# UCirKitUserStudy2.net
KiCad netlist of a schematic drawn in EAGLE
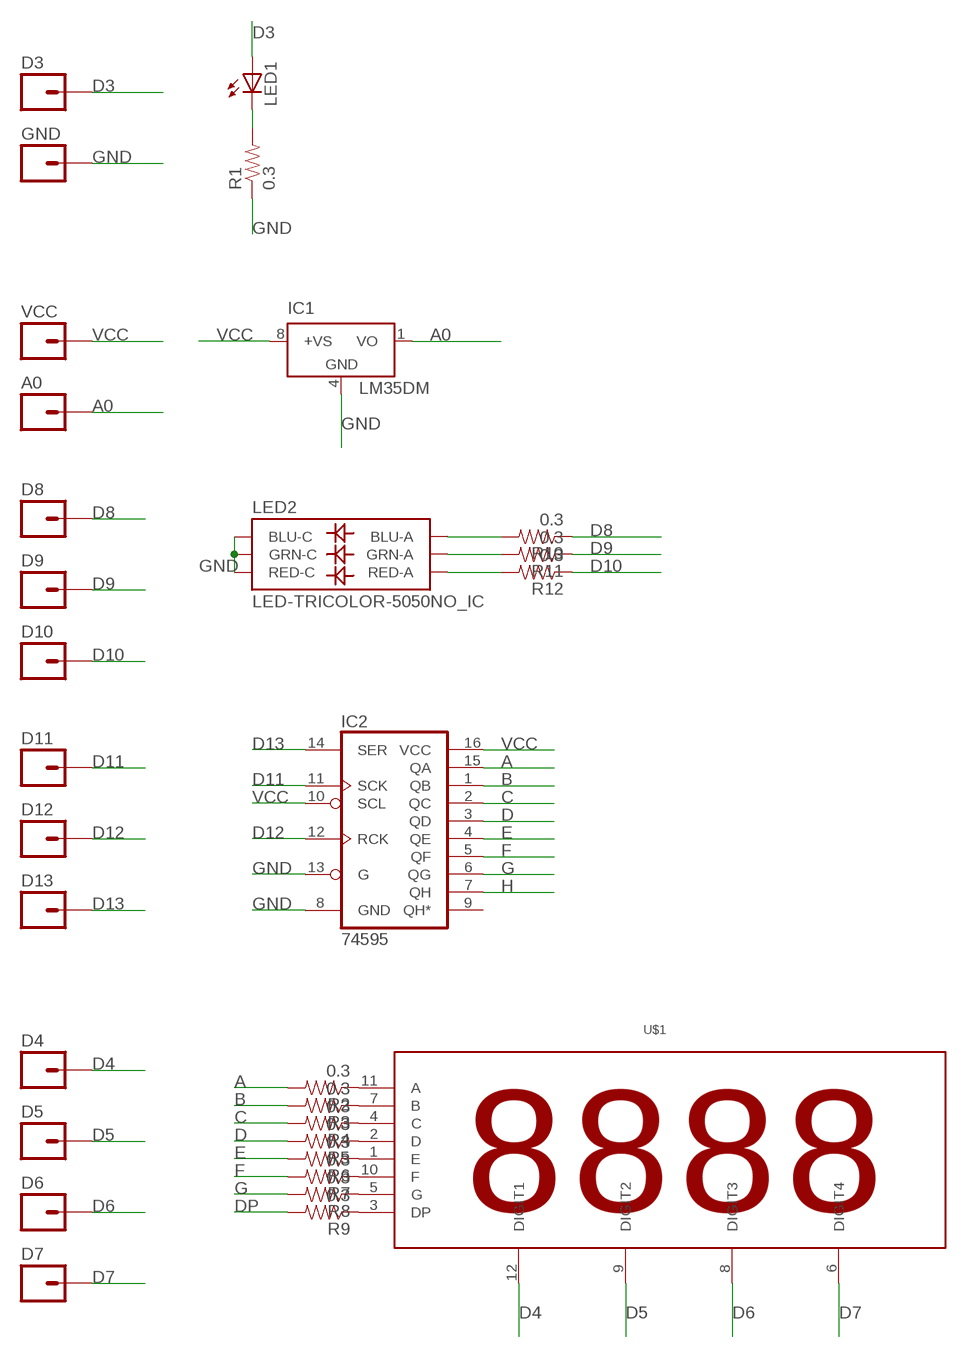
[diagram p0: schematic, sheet 1]

(export (version "E")
  (design (tool "Eeschema 10.0.6"))
  (components
    (comp (ref "A0")
      (value "M01PTH")
      (footprint "eagle-import:1X01")
      (libsource (lib "eagle-import") (part "M01PTH"))
    )
    (comp (ref "D3")
      (value "M01PTH")
      (footprint "eagle-import:1X01")
      (libsource (lib "eagle-import") (part "M01PTH"))
    )
    (comp (ref "D4")
      (value "M01PTH")
      (footprint "eagle-import:1X01")
      (libsource (lib "eagle-import") (part "M01PTH"))
    )
    (comp (ref "D5")
      (value "M01PTH")
      (footprint "eagle-import:1X01")
      (libsource (lib "eagle-import") (part "M01PTH"))
    )
    (comp (ref "D6")
      (value "M01PTH")
      (footprint "eagle-import:1X01")
      (libsource (lib "eagle-import") (part "M01PTH"))
    )
    (comp (ref "D7")
      (value "M01PTH")
      (footprint "eagle-import:1X01")
      (libsource (lib "eagle-import") (part "M01PTH"))
    )
    (comp (ref "D8")
      (value "M01PTH")
      (footprint "eagle-import:1X01")
      (libsource (lib "eagle-import") (part "M01PTH"))
    )
    (comp (ref "D9")
      (value "M01PTH")
      (footprint "eagle-import:1X01")
      (libsource (lib "eagle-import") (part "M01PTH"))
    )
    (comp (ref "D10")
      (value "M01PTH")
      (footprint "eagle-import:1X01")
      (libsource (lib "eagle-import") (part "M01PTH"))
    )
    (comp (ref "D11")
      (value "M01PTH")
      (footprint "eagle-import:1X01")
      (libsource (lib "eagle-import") (part "M01PTH"))
    )
    (comp (ref "D12")
      (value "M01PTH")
      (footprint "eagle-import:1X01")
      (libsource (lib "eagle-import") (part "M01PTH"))
    )
    (comp (ref "D13")
      (value "M01PTH")
      (footprint "eagle-import:1X01")
      (libsource (lib "eagle-import") (part "M01PTH"))
    )
    (comp (ref "GND")
      (value "M01PTH")
      (footprint "eagle-import:1X01")
      (libsource (lib "eagle-import") (part "M01PTH"))
    )
    (comp (ref "IC1")
      (value "LM35DM")
      (footprint "eagle-import:SO08")
      (libsource (lib "eagle-import") (part "LM35DM"))
    )
    (comp (ref "IC2")
      (value "74595")
      (footprint "eagle-import:TSSOP16")
      (libsource (lib "eagle-import") (part "74595"))
    )
    (comp (ref "LED1")
      (value "LEDCHIPLED_0805")
      (footprint "eagle-import:CHIPLED_0805")
      (libsource (lib "eagle-import") (part "LEDCHIPLED_0805"))
    )
    (comp (ref "LED2")
      (value "LED-TRICOLOR-5050NO_IC")
      (footprint "eagle-import:LED-TRICOLOR-5050")
      (libsource (lib "eagle-import") (part "LED-TRICOLOR-5050NO_IC"))
    )
    (comp (ref "R1")
      (value "0.3")
      (footprint "eagle-import:0805")
      (libsource (lib "eagle-import") (part "0.3OHM-1/8W-1%(0805)"))
    )
    (comp (ref "R2")
      (value "0.3")
      (footprint "eagle-import:0805")
      (libsource (lib "eagle-import") (part "0.3OHM-1/8W-1%(0805)"))
    )
    (comp (ref "R3")
      (value "0.3")
      (footprint "eagle-import:0805")
      (libsource (lib "eagle-import") (part "0.3OHM-1/8W-1%(0805)"))
    )
    (comp (ref "R4")
      (value "0.3")
      (footprint "eagle-import:0805")
      (libsource (lib "eagle-import") (part "0.3OHM-1/8W-1%(0805)"))
    )
    (comp (ref "R5")
      (value "0.3")
      (footprint "eagle-import:0805")
      (libsource (lib "eagle-import") (part "0.3OHM-1/8W-1%(0805)"))
    )
    (comp (ref "R6")
      (value "0.3")
      (footprint "eagle-import:0805")
      (libsource (lib "eagle-import") (part "0.3OHM-1/8W-1%(0805)"))
    )
    (comp (ref "R7")
      (value "0.3")
      (footprint "eagle-import:0805")
      (libsource (lib "eagle-import") (part "0.3OHM-1/8W-1%(0805)"))
    )
    (comp (ref "R8")
      (value "0.3")
      (footprint "eagle-import:0805")
      (libsource (lib "eagle-import") (part "0.3OHM-1/8W-1%(0805)"))
    )
    (comp (ref "R9")
      (value "0.3")
      (footprint "eagle-import:0805")
      (libsource (lib "eagle-import") (part "0.3OHM-1/8W-1%(0805)"))
    )
    (comp (ref "R10")
      (value "0.3")
      (footprint "eagle-import:0805")
      (libsource (lib "eagle-import") (part "0.3OHM-1/8W-1%(0805)"))
    )
    (comp (ref "R11")
      (value "0.3")
      (footprint "eagle-import:0805")
      (libsource (lib "eagle-import") (part "0.3OHM-1/8W-1%(0805)"))
    )
    (comp (ref "R12")
      (value "0.3")
      (footprint "eagle-import:0805")
      (libsource (lib "eagle-import") (part "0.3OHM-1/8W-1%(0805)"))
    )
    (comp (ref "U$1")
      (value "4DIGIT_SEVEN_SEGMENT4DIGIT_SEVEN_SEGMENT_FAR_PINS")
      (footprint "eagle-import:4DIGIT_SEVEN_SEGMENT_FAR_PINS")
      (libsource (lib "eagle-import") (part "4DIGIT_SEVEN_SEGMENT4DIGIT_SEVEN_SEGMENT_FAR_PINS"))
    )
    (comp (ref "VCC")
      (value "M01PTH")
      (footprint "eagle-import:1X01")
      (libsource (lib "eagle-import") (part "M01PTH"))
    )
  )
  (nets
    (net (code "1") (name "/A") (class "Default")
      (node (ref "IC2") (pin "15") (pinfunction "QA_15") (pintype "tri_state"))
      (node (ref "R2") (pin "2") (pinfunction "2_2") (pintype "passive"))
    )
    (net (code "2") (name "/A0") (class "Default")
      (node (ref "A0") (pin "1") (pinfunction "1_1") (pintype "passive"))
      (node (ref "IC1") (pin "1") (pinfunction "VO_1") (pintype "input"))
    )
    (net (code "3") (name "/B") (class "Default")
      (node (ref "IC2") (pin "1") (pinfunction "QB_1") (pintype "tri_state"))
      (node (ref "R3") (pin "2") (pinfunction "2_2") (pintype "passive"))
    )
    (net (code "4") (name "/C") (class "Default")
      (node (ref "IC2") (pin "2") (pinfunction "QC_2") (pintype "tri_state"))
      (node (ref "R4") (pin "2") (pinfunction "2_2") (pintype "passive"))
    )
    (net (code "5") (name "/D") (class "Default")
      (node (ref "IC2") (pin "3") (pinfunction "QD_3") (pintype "tri_state"))
      (node (ref "R5") (pin "2") (pinfunction "2_2") (pintype "passive"))
    )
    (net (code "6") (name "/D3") (class "Default")
      (node (ref "D3") (pin "1") (pinfunction "1_1") (pintype "passive"))
      (node (ref "LED1") (pin "A") (pinfunction "A_A") (pintype "passive"))
    )
    (net (code "7") (name "/D4") (class "Default")
      (node (ref "D4") (pin "1") (pinfunction "1_1") (pintype "passive"))
      (node (ref "U$1") (pin "12") (pinfunction "DIGIT1_12") (pintype "bidirectional"))
    )
    (net (code "8") (name "/D5") (class "Default")
      (node (ref "D5") (pin "1") (pinfunction "1_1") (pintype "passive"))
      (node (ref "U$1") (pin "9") (pinfunction "DIGIT2_9") (pintype "bidirectional"))
    )
    (net (code "9") (name "/D6") (class "Default")
      (node (ref "D6") (pin "1") (pinfunction "1_1") (pintype "passive"))
      (node (ref "U$1") (pin "8") (pinfunction "DIGIT3_8") (pintype "bidirectional"))
    )
    (net (code "10") (name "/D7") (class "Default")
      (node (ref "D7") (pin "1") (pinfunction "1_1") (pintype "passive"))
      (node (ref "U$1") (pin "6") (pinfunction "DIGIT4_6") (pintype "bidirectional"))
    )
    (net (code "11") (name "/D8") (class "Default")
      (node (ref "D8") (pin "1") (pinfunction "1_1") (pintype "passive"))
      (node (ref "R10") (pin "1") (pinfunction "1_1") (pintype "passive"))
    )
    (net (code "12") (name "/D9") (class "Default")
      (node (ref "D9") (pin "1") (pinfunction "1_1") (pintype "passive"))
      (node (ref "R11") (pin "1") (pinfunction "1_1") (pintype "passive"))
    )
    (net (code "13") (name "/D10") (class "Default")
      (node (ref "D10") (pin "1") (pinfunction "1_1") (pintype "passive"))
      (node (ref "R12") (pin "1") (pinfunction "1_1") (pintype "passive"))
    )
    (net (code "14") (name "/D11") (class "Default")
      (node (ref "D11") (pin "1") (pinfunction "1_1") (pintype "passive"))
      (node (ref "IC2") (pin "11") (pinfunction "SCK_11") (pintype "input"))
    )
    (net (code "15") (name "/D12") (class "Default")
      (node (ref "D12") (pin "1") (pinfunction "1_1") (pintype "passive"))
      (node (ref "IC2") (pin "12") (pinfunction "RCK_12") (pintype "input"))
    )
    (net (code "16") (name "/D13") (class "Default")
      (node (ref "D13") (pin "1") (pinfunction "1_1") (pintype "passive"))
      (node (ref "IC2") (pin "14") (pinfunction "SER_14") (pintype "input"))
    )
    (net (code "17") (name "/DP") (class "Default")
      (node (ref "R9") (pin "2") (pinfunction "2_2") (pintype "passive"))
    )
    (net (code "18") (name "/E") (class "Default")
      (node (ref "IC2") (pin "4") (pinfunction "QE_4") (pintype "tri_state"))
      (node (ref "R6") (pin "2") (pinfunction "2_2") (pintype "passive"))
    )
    (net (code "19") (name "/F") (class "Default")
      (node (ref "IC2") (pin "5") (pinfunction "QF_5") (pintype "tri_state"))
      (node (ref "R7") (pin "2") (pinfunction "2_2") (pintype "passive"))
    )
    (net (code "20") (name "/G") (class "Default")
      (node (ref "IC2") (pin "6") (pinfunction "QG_6") (pintype "tri_state"))
      (node (ref "R8") (pin "2") (pinfunction "2_2") (pintype "passive"))
    )
    (net (code "21") (name "/GND") (class "Default")
      (node (ref "GND") (pin "1") (pinfunction "1_1") (pintype "passive"))
      (node (ref "IC1") (pin "4") (pinfunction "GND_4") (pintype "power_in"))
      (node (ref "IC2") (pin "13") (pinfunction "G_13") (pintype "input"))
      (node (ref "IC2") (pin "8") (pinfunction "GND_8") (pintype "power_in"))
      (node (ref "LED2") (pin "4") (pinfunction "BLU-C_4") (pintype "bidirectional"))
      (node (ref "LED2") (pin "5") (pinfunction "RED-C_5") (pintype "bidirectional"))
      (node (ref "LED2") (pin "6") (pinfunction "GRN-C_6") (pintype "bidirectional"))
      (node (ref "R1") (pin "1") (pinfunction "1_1") (pintype "passive"))
    )
    (net (code "22") (name "/H") (class "Default")
      (node (ref "IC2") (pin "7") (pinfunction "QH_7") (pintype "tri_state"))
    )
    (net (code "23") (name "/VCC") (class "Default")
      (node (ref "IC1") (pin "8") (pinfunction "+VS_8") (pintype "input"))
      (node (ref "IC2") (pin "10") (pinfunction "SCL_10") (pintype "input"))
      (node (ref "IC2") (pin "16") (pinfunction "VCC_16") (pintype "power_in"))
      (node (ref "VCC") (pin "1") (pinfunction "1_1") (pintype "passive"))
    )
    (net (code "24") (name "Net-(LED1-PadC)") (class "Default")
      (node (ref "LED1") (pin "C") (pinfunction "C_C") (pintype "passive"))
      (node (ref "R1") (pin "2") (pinfunction "2_2") (pintype "passive"))
    )
    (net (code "25") (name "Net-(LED2-BLU-A)") (class "Default")
      (node (ref "LED2") (pin "3") (pinfunction "BLU-A_3") (pintype "bidirectional"))
      (node (ref "R10") (pin "2") (pinfunction "2_2") (pintype "passive"))
    )
    (net (code "26") (name "Net-(LED2-GRN-A)") (class "Default")
      (node (ref "LED2") (pin "1") (pinfunction "GRN-A_1") (pintype "bidirectional"))
      (node (ref "R11") (pin "2") (pinfunction "2_2") (pintype "passive"))
    )
    (net (code "27") (name "Net-(LED2-RED-A)") (class "Default")
      (node (ref "LED2") (pin "2") (pinfunction "RED-A_2") (pintype "bidirectional"))
      (node (ref "R12") (pin "2") (pinfunction "2_2") (pintype "passive"))
    )
    (net (code "28") (name "Net-(U$1-A)") (class "Default")
      (node (ref "R2") (pin "1") (pinfunction "1_1") (pintype "passive"))
      (node (ref "U$1") (pin "11") (pinfunction "A_11") (pintype "bidirectional"))
    )
    (net (code "29") (name "Net-(U$1-B)") (class "Default")
      (node (ref "R3") (pin "1") (pinfunction "1_1") (pintype "passive"))
      (node (ref "U$1") (pin "7") (pinfunction "B_7") (pintype "bidirectional"))
    )
    (net (code "30") (name "Net-(U$1-C)") (class "Default")
      (node (ref "R4") (pin "1") (pinfunction "1_1") (pintype "passive"))
      (node (ref "U$1") (pin "4") (pinfunction "C_4") (pintype "bidirectional"))
    )
    (net (code "31") (name "Net-(U$1-D)") (class "Default")
      (node (ref "R5") (pin "1") (pinfunction "1_1") (pintype "passive"))
      (node (ref "U$1") (pin "2") (pinfunction "D_2") (pintype "bidirectional"))
    )
    (net (code "32") (name "Net-(U$1-DP)") (class "Default")
      (node (ref "R9") (pin "1") (pinfunction "1_1") (pintype "passive"))
      (node (ref "U$1") (pin "3") (pinfunction "DP_3") (pintype "bidirectional"))
    )
    (net (code "33") (name "Net-(U$1-E)") (class "Default")
      (node (ref "R6") (pin "1") (pinfunction "1_1") (pintype "passive"))
      (node (ref "U$1") (pin "1") (pinfunction "E_1") (pintype "bidirectional"))
    )
    (net (code "34") (name "Net-(U$1-F)") (class "Default")
      (node (ref "R7") (pin "1") (pinfunction "1_1") (pintype "passive"))
      (node (ref "U$1") (pin "10") (pinfunction "F_10") (pintype "bidirectional"))
    )
    (net (code "35") (name "Net-(U$1-G)") (class "Default")
      (node (ref "R8") (pin "1") (pinfunction "1_1") (pintype "passive"))
      (node (ref "U$1") (pin "5") (pinfunction "G_5") (pintype "bidirectional"))
    )
    (net (code "36") (name "unconnected-(IC2-QH*-Pad9)") (class "Default")
      (node (ref "IC2") (pin "9") (pinfunction "QH*_9") (pintype "tri_state"))
    )
  )
)
